# Main_Board_rev3.net
KiCad netlist of a schematic drawn in Altium Designer
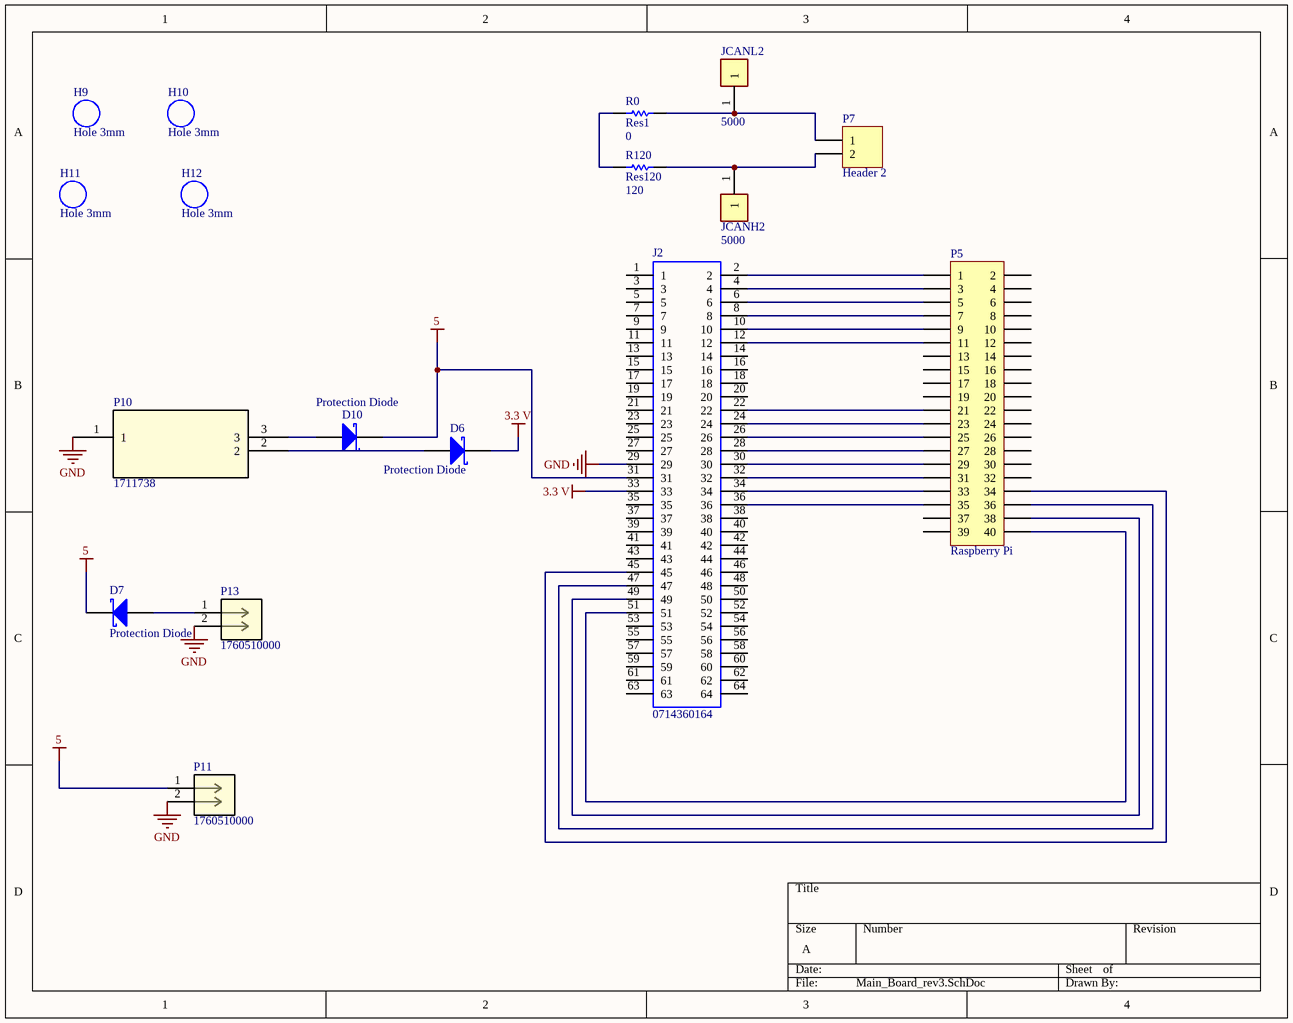
[diagram p0: Main_Board_rev3.SchDoc]

(export (version "E")
  (design (tool "Eeschema 10.0.6"))
  (components
    (comp (ref "D6")
      (value "Protection Diode")
      (footprint "TO-220AC")
      (description "Schottky Rectifier")
      (fields (field (name "PUBLISHER") "Altium Limited"))
      (libsource (lib "Miscellaneous Devices") (part "Diode 10TQ035"))
    )
    (comp (ref "D7")
      (value "Protection Diode")
      (footprint "TO-220AC")
      (description "Schottky Rectifier")
      (fields (field (name "PUBLISHER") "Altium Limited"))
      (libsource (lib "Miscellaneous Devices") (part "Diode 10TQ035"))
    )
    (comp (ref "D10")
      (value "Protection Diode")
      (footprint "TO-220AC")
      (description "Schottky Rectifier")
      (fields (field (name "PUBLISHER") "Altium Limited"))
      (libsource (lib "Miscellaneous Devices") (part "Diode 10TQ035"))
    )
    (comp (ref "H9")
      (value "Hole 3mm")
      (footprint "Hole 3mm")
      (libsource (lib "ECE LIB 21") (part "Hole 3mm"))
    )
    (comp (ref "H10")
      (value "Hole 3mm")
      (footprint "Hole 3mm")
      (libsource (lib "ECE LIB 21") (part "Hole 3mm"))
    )
    (comp (ref "H11")
      (value "Hole 3mm")
      (footprint "Hole 3mm")
      (libsource (lib "ECE LIB 21") (part "Hole 3mm"))
    )
    (comp (ref "H12")
      (value "Hole 3mm")
      (footprint "Hole 3mm")
      (libsource (lib "ECE LIB 21") (part "Hole 3mm"))
    )
    (comp (ref "J2")
      (value "0714360164")
      (footprint "0714360164")
      (description "Board to Board & Mezzanine Connectors 1.00MM PLG 02X32P VT SMT")
      (libsource (lib "0714360164") (part "0714360164"))
    )
    (comp (ref "JCANH2")
      (value "5000")
      (footprint "KEYSTONE_5000")
      (fields (field (name "MF") "Keystone"))
      (libsource (lib "5000") (part "5000"))
    )
    (comp (ref "JCANL2")
      (value "5000")
      (footprint "KEYSTONE_5000")
      (fields (field (name "MF") "Keystone"))
      (libsource (lib "") (part "5000_1"))
    )
    (comp (ref "P5")
      (value "Raspberry Pi")
      (footprint "HDR2X20")
      (description "Header, 20-Pin, Dual row")
      (fields (field (name "PUBLISHER") "Altium Limited"))
      (libsource (lib "Miscellaneous Connectors") (part "Header 20X2"))
    )
    (comp (ref "P7")
      (value "Header 2")
      (footprint "HDR1X2")
      (description "Header, 2-Pin")
      (fields (field (name "PUBLISHER") "Altium Limited"))
      (libsource (lib "Miscellaneous Connectors") (part "Header 2"))
    )
    (comp (ref "P10")
      (value "1711738")
      (footprint "1711738_PXC")
      (description "No Description Available")
      (fields (field (name "COPYRIGHT") "Copyright (C) 2022 Ultra Librarian. All rights reserved."))
      (libsource (lib "1711738") (part "1711738"))
    )
    (comp (ref "P11")
      (value "1760510000")
      (footprint "CONN2_1760510000_WED")
      (description "No Description Available")
      (fields (field (name "COPYRIGHT") "Copyright (C) 2022 Ultra Librarian. All rights reserved."))
      (libsource (lib "1760510000") (part "1760510000"))
    )
    (comp (ref "P13")
      (value "1760510000")
      (footprint "CONN2_1760510000_WED")
      (description "No Description Available")
      (fields (field (name "COPYRIGHT") "Copyright (C) 2022 Ultra Librarian. All rights reserved."))
      (libsource (lib "1760510000") (part "1760510000"))
    )
    (comp (ref "R0")
      (value "Res1")
      (footprint "AXIAL-0.3")
      (description "Resistor")
      (fields (field (name "ALTIUM_VALUE") "0") (field (name "PUBLISHER") "Altium Limited"))
      (libsource (lib "Miscellaneous Devices") (part "Res1"))
    )
    (comp (ref "R120")
      (value "Res120")
      (footprint "AXIAL-0.3")
      (description "Resistor")
      (fields (field (name "ALTIUM_VALUE") "120") (field (name "PUBLISHER") "Altium Limited"))
      (libsource (lib "Miscellaneous Devices") (part "Res1"))
    )
  )
  (nets
    (net (code "1") (name "3.3 V") (class "Default")
      (node (ref "D6") (pin "1") (pinfunction "K_1") (pintype "passive"))
      (node (ref "J2") (pin "33") (pinfunction "33_33") (pintype "passive"))
    )
    (net (code "2") (name "5") (class "Default")
      (node (ref "D10") (pin "1") (pinfunction "K_1") (pintype "passive"))
      (node (ref "D7") (pin "1") (pinfunction "K_1") (pintype "passive"))
      (node (ref "J2") (pin "31") (pinfunction "31_31") (pintype "passive"))
      (node (ref "P11") (pin "1") (pinfunction "1_1") (pintype "passive"))
    )
    (net (code "3") (name "GND") (class "Default")
      (node (ref "J2") (pin "29") (pinfunction "29_29") (pintype "passive"))
      (node (ref "P10") (pin "1") (pinfunction "1_1") (pintype "passive"))
      (node (ref "P11") (pin "2") (pinfunction "2_2") (pintype "passive"))
      (node (ref "P13") (pin "2") (pinfunction "2_2") (pintype "passive"))
    )
    (net (code "4") (name "Net-(D6-A)") (class "Default")
      (node (ref "D6") (pin "3") (pinfunction "A_3") (pintype "passive"))
      (node (ref "P10") (pin "2") (pinfunction "2_2") (pintype "passive"))
    )
    (net (code "5") (name "Net-(D7-A)") (class "Default")
      (node (ref "D7") (pin "3") (pinfunction "A_3") (pintype "passive"))
      (node (ref "P13") (pin "1") (pinfunction "1_1") (pintype "passive"))
    )
    (net (code "6") (name "Net-(D10-A)") (class "Default")
      (node (ref "D10") (pin "3") (pinfunction "A_3") (pintype "passive"))
      (node (ref "P10") (pin "3") (pinfunction "3_3") (pintype "passive"))
    )
    (net (code "7") (name "Net-(J2-Pad2)") (class "Default")
      (node (ref "J2") (pin "2") (pinfunction "2_2") (pintype "passive"))
      (node (ref "P5") (pin "1") (pinfunction "1_1") (pintype "passive"))
    )
    (net (code "8") (name "Net-(J2-Pad4)") (class "Default")
      (node (ref "J2") (pin "4") (pinfunction "4_4") (pintype "passive"))
      (node (ref "P5") (pin "3") (pinfunction "3_3") (pintype "passive"))
    )
    (net (code "9") (name "Net-(J2-Pad6)") (class "Default")
      (node (ref "J2") (pin "6") (pinfunction "6_6") (pintype "passive"))
      (node (ref "P5") (pin "5") (pinfunction "5_5") (pintype "passive"))
    )
    (net (code "10") (name "Net-(J2-Pad8)") (class "Default")
      (node (ref "J2") (pin "8") (pinfunction "8_8") (pintype "passive"))
      (node (ref "P5") (pin "7") (pinfunction "7_7") (pintype "passive"))
    )
    (net (code "11") (name "Net-(J2-Pad10)") (class "Default")
      (node (ref "J2") (pin "10") (pinfunction "10_10") (pintype "passive"))
      (node (ref "P5") (pin "9") (pinfunction "9_9") (pintype "passive"))
    )
    (net (code "12") (name "Net-(J2-Pad12)") (class "Default")
      (node (ref "J2") (pin "12") (pinfunction "12_12") (pintype "passive"))
      (node (ref "P5") (pin "11") (pinfunction "11_11") (pintype "passive"))
    )
    (net (code "13") (name "Net-(J2-Pad22)") (class "Default")
      (node (ref "J2") (pin "22") (pinfunction "22_22") (pintype "passive"))
      (node (ref "P5") (pin "21") (pinfunction "21_21") (pintype "passive"))
    )
    (net (code "14") (name "Net-(J2-Pad24)") (class "Default")
      (node (ref "J2") (pin "24") (pinfunction "24_24") (pintype "passive"))
      (node (ref "P5") (pin "23") (pinfunction "23_23") (pintype "passive"))
    )
    (net (code "15") (name "Net-(J2-Pad26)") (class "Default")
      (node (ref "J2") (pin "26") (pinfunction "26_26") (pintype "passive"))
      (node (ref "P5") (pin "25") (pinfunction "25_25") (pintype "passive"))
    )
    (net (code "16") (name "Net-(J2-Pad28)") (class "Default")
      (node (ref "J2") (pin "28") (pinfunction "28_28") (pintype "passive"))
      (node (ref "P5") (pin "27") (pinfunction "27_27") (pintype "passive"))
    )
    (net (code "17") (name "Net-(J2-Pad30)") (class "Default")
      (node (ref "J2") (pin "30") (pinfunction "30_30") (pintype "passive"))
      (node (ref "P5") (pin "29") (pinfunction "29_29") (pintype "passive"))
    )
    (net (code "18") (name "Net-(J2-Pad32)") (class "Default")
      (node (ref "J2") (pin "32") (pinfunction "32_32") (pintype "passive"))
      (node (ref "P5") (pin "31") (pinfunction "31_31") (pintype "passive"))
    )
    (net (code "19") (name "Net-(J2-Pad34)") (class "Default")
      (node (ref "J2") (pin "34") (pinfunction "34_34") (pintype "passive"))
      (node (ref "P5") (pin "33") (pinfunction "33_33") (pintype "passive"))
    )
    (net (code "20") (name "Net-(J2-Pad36)") (class "Default")
      (node (ref "J2") (pin "36") (pinfunction "36_36") (pintype "passive"))
      (node (ref "P5") (pin "35") (pinfunction "35_35") (pintype "passive"))
    )
    (net (code "21") (name "Net-(J2-Pad45)") (class "Default")
      (node (ref "J2") (pin "45") (pinfunction "45_45") (pintype "passive"))
      (node (ref "P5") (pin "34") (pinfunction "34_34") (pintype "passive"))
    )
    (net (code "22") (name "Net-(J2-Pad47)") (class "Default")
      (node (ref "J2") (pin "47") (pinfunction "47_47") (pintype "passive"))
      (node (ref "P5") (pin "36") (pinfunction "36_36") (pintype "passive"))
    )
    (net (code "23") (name "Net-(J2-Pad49)") (class "Default")
      (node (ref "J2") (pin "49") (pinfunction "49_49") (pintype "passive"))
      (node (ref "P5") (pin "38") (pinfunction "38_38") (pintype "passive"))
    )
    (net (code "24") (name "Net-(J2-Pad51)") (class "Default")
      (node (ref "J2") (pin "51") (pinfunction "51_51") (pintype "passive"))
      (node (ref "P5") (pin "40") (pinfunction "40_40") (pintype "passive"))
    )
    (net (code "25") (name "Net-(JCANH2-Pad1)") (class "Default")
      (node (ref "JCANH2") (pin "1") (pinfunction "1_1") (pintype "passive"))
      (node (ref "P7") (pin "2") (pinfunction "2_2") (pintype "passive"))
      (node (ref "R120") (pin "2") (pinfunction "2_2") (pintype "passive"))
    )
    (net (code "26") (name "Net-(JCANL2-Pad1)") (class "Default")
      (node (ref "JCANL2") (pin "1") (pinfunction "1_1") (pintype "passive"))
      (node (ref "P7") (pin "1") (pinfunction "1_1") (pintype "passive"))
      (node (ref "R0") (pin "2") (pinfunction "2_2") (pintype "passive"))
    )
    (net (code "27") (name "Net-(R0-Pad1)") (class "Default")
      (node (ref "R0") (pin "1") (pinfunction "1_1") (pintype "passive"))
      (node (ref "R120") (pin "1") (pinfunction "1_1") (pintype "passive"))
    )
    (net (code "28") (name "unconnected-(J2-Pad1)") (class "Default")
      (node (ref "J2") (pin "1") (pinfunction "1_1") (pintype "passive"))
    )
    (net (code "29") (name "unconnected-(J2-Pad3)") (class "Default")
      (node (ref "J2") (pin "3") (pinfunction "3_3") (pintype "passive"))
    )
    (net (code "30") (name "unconnected-(J2-Pad5)") (class "Default")
      (node (ref "J2") (pin "5") (pinfunction "5_5") (pintype "passive"))
    )
    (net (code "31") (name "unconnected-(J2-Pad7)") (class "Default")
      (node (ref "J2") (pin "7") (pinfunction "7_7") (pintype "passive"))
    )
    (net (code "32") (name "unconnected-(J2-Pad9)") (class "Default")
      (node (ref "J2") (pin "9") (pinfunction "9_9") (pintype "passive"))
    )
    (net (code "33") (name "unconnected-(J2-Pad11)") (class "Default")
      (node (ref "J2") (pin "11") (pinfunction "11_11") (pintype "passive"))
    )
    (net (code "34") (name "unconnected-(J2-Pad13)") (class "Default")
      (node (ref "J2") (pin "13") (pinfunction "13_13") (pintype "passive"))
    )
    (net (code "35") (name "unconnected-(J2-Pad14)") (class "Default")
      (node (ref "J2") (pin "14") (pinfunction "14_14") (pintype "passive"))
    )
    (net (code "36") (name "unconnected-(J2-Pad15)") (class "Default")
      (node (ref "J2") (pin "15") (pinfunction "15_15") (pintype "passive"))
    )
    (net (code "37") (name "unconnected-(J2-Pad16)") (class "Default")
      (node (ref "J2") (pin "16") (pinfunction "16_16") (pintype "passive"))
    )
    (net (code "38") (name "unconnected-(J2-Pad17)") (class "Default")
      (node (ref "J2") (pin "17") (pinfunction "17_17") (pintype "passive"))
    )
    (net (code "39") (name "unconnected-(J2-Pad18)") (class "Default")
      (node (ref "J2") (pin "18") (pinfunction "18_18") (pintype "passive"))
    )
    (net (code "40") (name "unconnected-(J2-Pad19)") (class "Default")
      (node (ref "J2") (pin "19") (pinfunction "19_19") (pintype "passive"))
    )
    (net (code "41") (name "unconnected-(J2-Pad20)") (class "Default")
      (node (ref "J2") (pin "20") (pinfunction "20_20") (pintype "passive"))
    )
    (net (code "42") (name "unconnected-(J2-Pad21)") (class "Default")
      (node (ref "J2") (pin "21") (pinfunction "21_21") (pintype "passive"))
    )
    (net (code "43") (name "unconnected-(J2-Pad23)") (class "Default")
      (node (ref "J2") (pin "23") (pinfunction "23_23") (pintype "passive"))
    )
    (net (code "44") (name "unconnected-(J2-Pad25)") (class "Default")
      (node (ref "J2") (pin "25") (pinfunction "25_25") (pintype "passive"))
    )
    (net (code "45") (name "unconnected-(J2-Pad27)") (class "Default")
      (node (ref "J2") (pin "27") (pinfunction "27_27") (pintype "passive"))
    )
    (net (code "46") (name "unconnected-(J2-Pad35)") (class "Default")
      (node (ref "J2") (pin "35") (pinfunction "35_35") (pintype "passive"))
    )
    (net (code "47") (name "unconnected-(J2-Pad37)") (class "Default")
      (node (ref "J2") (pin "37") (pinfunction "37_37") (pintype "passive"))
    )
    (net (code "48") (name "unconnected-(J2-Pad38)") (class "Default")
      (node (ref "J2") (pin "38") (pinfunction "38_38") (pintype "passive"))
    )
    (net (code "49") (name "unconnected-(J2-Pad39)") (class "Default")
      (node (ref "J2") (pin "39") (pinfunction "39_39") (pintype "passive"))
    )
    (net (code "50") (name "unconnected-(J2-Pad40)") (class "Default")
      (node (ref "J2") (pin "40") (pinfunction "40_40") (pintype "passive"))
    )
    (net (code "51") (name "unconnected-(J2-Pad41)") (class "Default")
      (node (ref "J2") (pin "41") (pinfunction "41_41") (pintype "passive"))
    )
    (net (code "52") (name "unconnected-(J2-Pad42)") (class "Default")
      (node (ref "J2") (pin "42") (pinfunction "42_42") (pintype "passive"))
    )
    (net (code "53") (name "unconnected-(J2-Pad43)") (class "Default")
      (node (ref "J2") (pin "43") (pinfunction "43_43") (pintype "passive"))
    )
    (net (code "54") (name "unconnected-(J2-Pad44)") (class "Default")
      (node (ref "J2") (pin "44") (pinfunction "44_44") (pintype "passive"))
    )
    (net (code "55") (name "unconnected-(J2-Pad46)") (class "Default")
      (node (ref "J2") (pin "46") (pinfunction "46_46") (pintype "passive"))
    )
    (net (code "56") (name "unconnected-(J2-Pad48)") (class "Default")
      (node (ref "J2") (pin "48") (pinfunction "48_48") (pintype "passive"))
    )
    (net (code "57") (name "unconnected-(J2-Pad50)") (class "Default")
      (node (ref "J2") (pin "50") (pinfunction "50_50") (pintype "passive"))
    )
    (net (code "58") (name "unconnected-(J2-Pad52)") (class "Default")
      (node (ref "J2") (pin "52") (pinfunction "52_52") (pintype "passive"))
    )
    (net (code "59") (name "unconnected-(J2-Pad53)") (class "Default")
      (node (ref "J2") (pin "53") (pinfunction "53_53") (pintype "passive"))
    )
    (net (code "60") (name "unconnected-(J2-Pad54)") (class "Default")
      (node (ref "J2") (pin "54") (pinfunction "54_54") (pintype "passive"))
    )
    (net (code "61") (name "unconnected-(J2-Pad55)") (class "Default")
      (node (ref "J2") (pin "55") (pinfunction "55_55") (pintype "passive"))
    )
    (net (code "62") (name "unconnected-(J2-Pad56)") (class "Default")
      (node (ref "J2") (pin "56") (pinfunction "56_56") (pintype "passive"))
    )
    (net (code "63") (name "unconnected-(J2-Pad57)") (class "Default")
      (node (ref "J2") (pin "57") (pinfunction "57_57") (pintype "passive"))
    )
    (net (code "64") (name "unconnected-(J2-Pad58)") (class "Default")
      (node (ref "J2") (pin "58") (pinfunction "58_58") (pintype "passive"))
    )
    (net (code "65") (name "unconnected-(J2-Pad59)") (class "Default")
      (node (ref "J2") (pin "59") (pinfunction "59_59") (pintype "passive"))
    )
    (net (code "66") (name "unconnected-(J2-Pad60)") (class "Default")
      (node (ref "J2") (pin "60") (pinfunction "60_60") (pintype "passive"))
    )
    (net (code "67") (name "unconnected-(J2-Pad61)") (class "Default")
      (node (ref "J2") (pin "61") (pinfunction "61_61") (pintype "passive"))
    )
    (net (code "68") (name "unconnected-(J2-Pad62)") (class "Default")
      (node (ref "J2") (pin "62") (pinfunction "62_62") (pintype "passive"))
    )
    (net (code "69") (name "unconnected-(J2-Pad63)") (class "Default")
      (node (ref "J2") (pin "63") (pinfunction "63_63") (pintype "passive"))
    )
    (net (code "70") (name "unconnected-(J2-Pad64)") (class "Default")
      (node (ref "J2") (pin "64") (pinfunction "64_64") (pintype "passive"))
    )
    (net (code "71") (name "unconnected-(P5-Pad2)") (class "Default")
      (node (ref "P5") (pin "2") (pinfunction "2_2") (pintype "passive"))
    )
    (net (code "72") (name "unconnected-(P5-Pad4)") (class "Default")
      (node (ref "P5") (pin "4") (pinfunction "4_4") (pintype "passive"))
    )
    (net (code "73") (name "unconnected-(P5-Pad6)") (class "Default")
      (node (ref "P5") (pin "6") (pinfunction "6_6") (pintype "passive"))
    )
    (net (code "74") (name "unconnected-(P5-Pad8)") (class "Default")
      (node (ref "P5") (pin "8") (pinfunction "8_8") (pintype "passive"))
    )
    (net (code "75") (name "unconnected-(P5-Pad10)") (class "Default")
      (node (ref "P5") (pin "10") (pinfunction "10_10") (pintype "passive"))
    )
    (net (code "76") (name "unconnected-(P5-Pad12)") (class "Default")
      (node (ref "P5") (pin "12") (pinfunction "12_12") (pintype "passive"))
    )
    (net (code "77") (name "unconnected-(P5-Pad13)") (class "Default")
      (node (ref "P5") (pin "13") (pinfunction "13_13") (pintype "passive"))
    )
    (net (code "78") (name "unconnected-(P5-Pad14)") (class "Default")
      (node (ref "P5") (pin "14") (pinfunction "14_14") (pintype "passive"))
    )
    (net (code "79") (name "unconnected-(P5-Pad15)") (class "Default")
      (node (ref "P5") (pin "15") (pinfunction "15_15") (pintype "passive"))
    )
    (net (code "80") (name "unconnected-(P5-Pad16)") (class "Default")
      (node (ref "P5") (pin "16") (pinfunction "16_16") (pintype "passive"))
    )
    (net (code "81") (name "unconnected-(P5-Pad17)") (class "Default")
      (node (ref "P5") (pin "17") (pinfunction "17_17") (pintype "passive"))
    )
    (net (code "82") (name "unconnected-(P5-Pad18)") (class "Default")
      (node (ref "P5") (pin "18") (pinfunction "18_18") (pintype "passive"))
    )
    (net (code "83") (name "unconnected-(P5-Pad19)") (class "Default")
      (node (ref "P5") (pin "19") (pinfunction "19_19") (pintype "passive"))
    )
    (net (code "84") (name "unconnected-(P5-Pad20)") (class "Default")
      (node (ref "P5") (pin "20") (pinfunction "20_20") (pintype "passive"))
    )
    (net (code "85") (name "unconnected-(P5-Pad22)") (class "Default")
      (node (ref "P5") (pin "22") (pinfunction "22_22") (pintype "passive"))
    )
    (net (code "86") (name "unconnected-(P5-Pad24)") (class "Default")
      (node (ref "P5") (pin "24") (pinfunction "24_24") (pintype "passive"))
    )
    (net (code "87") (name "unconnected-(P5-Pad26)") (class "Default")
      (node (ref "P5") (pin "26") (pinfunction "26_26") (pintype "passive"))
    )
    (net (code "88") (name "unconnected-(P5-Pad28)") (class "Default")
      (node (ref "P5") (pin "28") (pinfunction "28_28") (pintype "passive"))
    )
    (net (code "89") (name "unconnected-(P5-Pad30)") (class "Default")
      (node (ref "P5") (pin "30") (pinfunction "30_30") (pintype "passive"))
    )
    (net (code "90") (name "unconnected-(P5-Pad32)") (class "Default")
      (node (ref "P5") (pin "32") (pinfunction "32_32") (pintype "passive"))
    )
    (net (code "91") (name "unconnected-(P5-Pad37)") (class "Default")
      (node (ref "P5") (pin "37") (pinfunction "37_37") (pintype "passive"))
    )
    (net (code "92") (name "unconnected-(P5-Pad39)") (class "Default")
      (node (ref "P5") (pin "39") (pinfunction "39_39") (pintype "passive"))
    )
  )
)
